# 09.net
KiCad netlist of a schematic drawn in Altium Designer
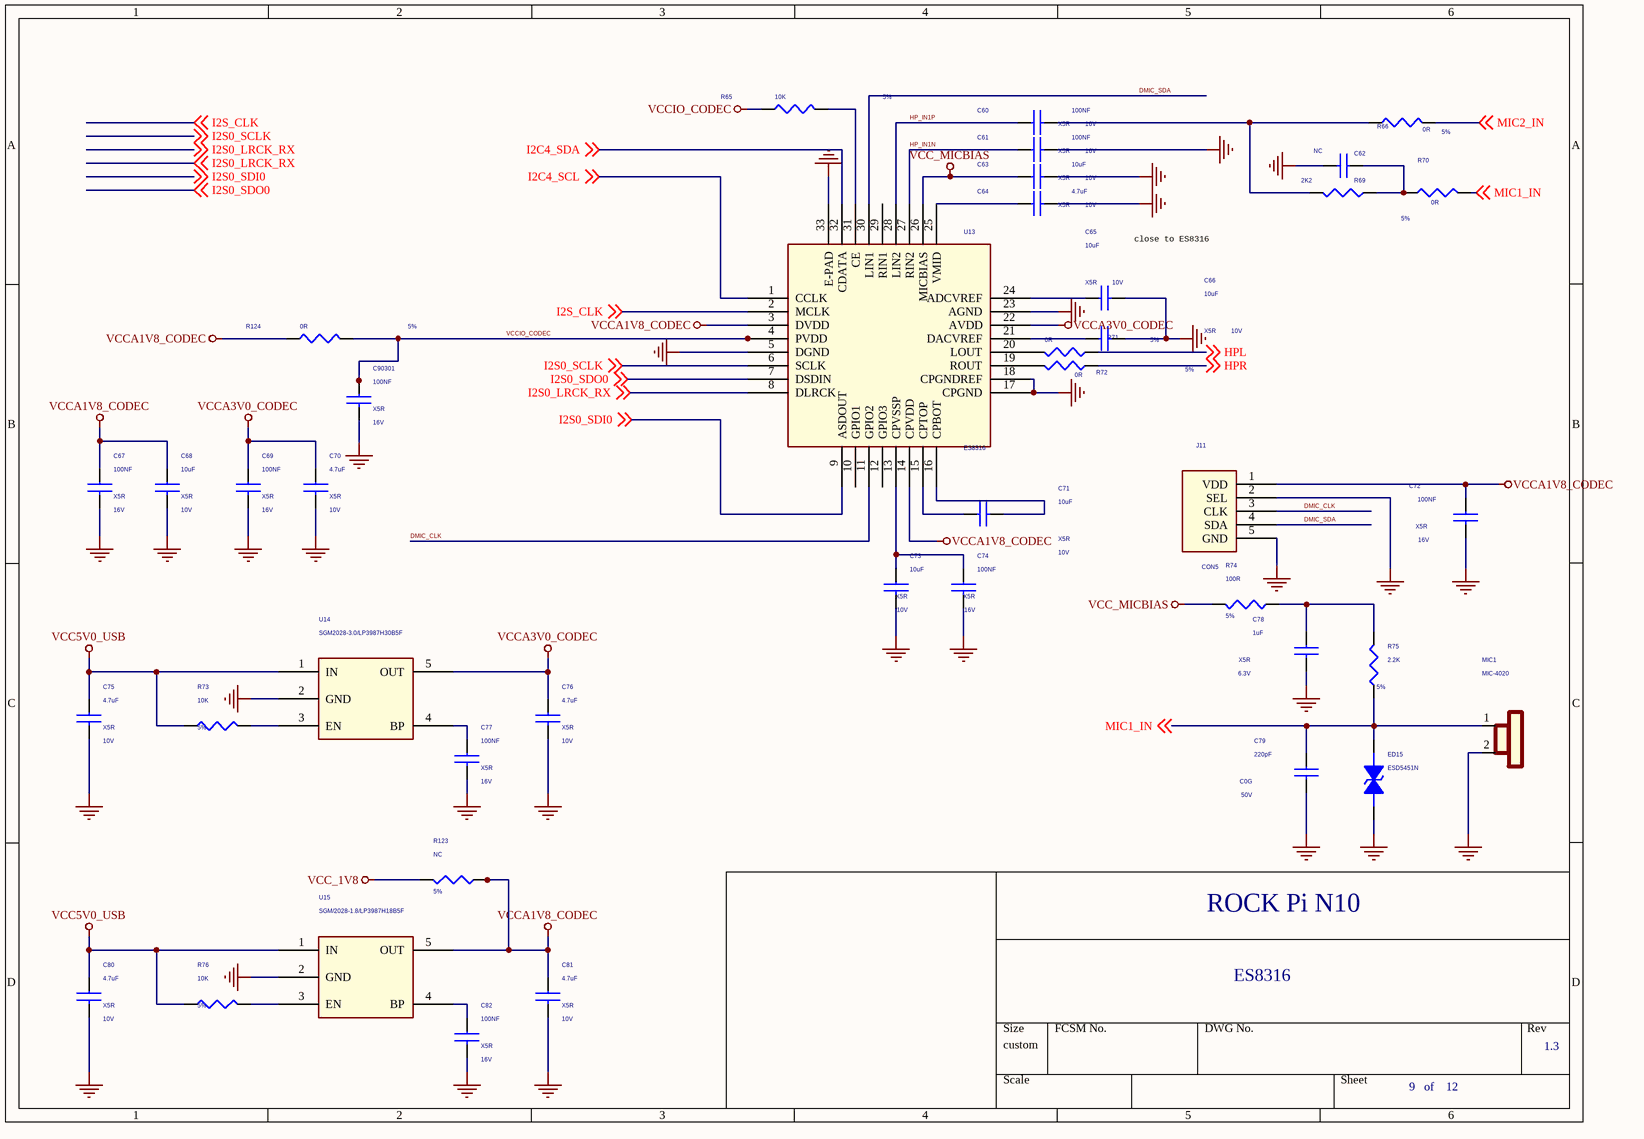
[diagram p0: 09.SchDoc]

(export (version "E")
  (design (tool "Eeschema 10.0.6"))
  (components
    (comp (ref "C60")
      (value "100NF")
      (footprint "C0402")
      (description "cap,100.00nF,+/-10%,16V,X5R,C0402")
      (fields
        (field (name "DIELECTRIC") "X5R")
        (field (name "VOLTAGE") "16V")
        (field (name "MANUFACTURER") "TDK")
        (field (name "TOLERANCE") "10%")
        (field (name "CREATED BY") "JJJ")
      )
      (libsource (lib "*") (part "CAP NP_2"))
    )
    (comp (ref "C61")
      (value "100NF")
      (footprint "C0402")
      (description "cap,100.00nF,+/-10%,16V,X5R,C0402")
      (fields
        (field (name "DIELECTRIC") "X5R")
        (field (name "VOLTAGE") "16V")
        (field (name "TOLERANCE") "10%")
        (field (name "MANUFACTURER") "TDK")
        (field (name "CREATED BY") "JJJ")
      )
      (libsource (lib "*") (part "CAP NP_2"))
    )
    (comp (ref "C62")
      (value "NC")
      (footprint "C0402")
      (description "RoHS CHIP CAP 0.1uF +10/-10% X7R")
      (libsource (lib "*") (part "CAP"))
    )
    (comp (ref "C63")
      (value "10uF")
      (footprint "C0603")
      (description "cap,10.00uF,+/-10%,10V,X5R,C0805")
      (fields
        (field (name "DIELECTRIC") "X5R")
        (field (name "VOLTAGE") "10V")
        (field (name "MANUFACTURER") "TDK")
        (field (name "TOLERANCE") "10%")
        (field (name "CREATED BY") "JJJ")
      )
      (libsource (lib "*") (part "CAP NP_2"))
    )
    (comp (ref "C64")
      (value "4.7uF")
      (footprint "C0402")
      (description "cap,4.70uF,+/-10%,10V,X5R,C0603")
      (fields
        (field (name "DIELECTRIC") "X5R")
        (field (name "VOLTAGE") "10V")
        (field (name "MANUFACTURER") "TDK")
        (field (name "TOLERANCE") "10%")
        (field (name "CREATED BY") "JJJ")
      )
      (libsource (lib "*") (part "CAP NP_2"))
    )
    (comp (ref "C65")
      (value "10uF")
      (footprint "C0603")
      (description "cap,10.00uF,+/-10%,10V,X5R,C0805")
      (fields
        (field (name "DIELECTRIC") "X5R")
        (field (name "VOLTAGE") "10V")
        (field (name "TOLERANCE") "10%")
        (field (name "MANUFACTURER") "TDK")
        (field (name "CREATED BY") "JJJ")
      )
      (libsource (lib "*") (part "CAP NP_2"))
    )
    (comp (ref "C66")
      (value "10uF")
      (footprint "C0603")
      (description "cap,10.00uF,+/-10%,10V,X5R,C0805")
      (fields
        (field (name "DIELECTRIC") "X5R")
        (field (name "VOLTAGE") "10V")
        (field (name "TOLERANCE") "10%")
        (field (name "MANUFACTURER") "TDK")
        (field (name "CREATED BY") "JJJ")
      )
      (libsource (lib "*") (part "CAP NP_2"))
    )
    (comp (ref "C67")
      (value "100NF")
      (footprint "C0402")
      (description "cap,100.00nF,+/-10%,16V,X5R,C0402")
      (fields
        (field (name "DIELECTRIC") "X5R")
        (field (name "VOLTAGE") "16V")
        (field (name "TOLERANCE") "10%")
        (field (name "MANUFACTURER") "TDK")
        (field (name "CREATED BY") "JJJ")
      )
      (libsource (lib "*") (part "CAP NP_2"))
    )
    (comp (ref "C68")
      (value "10uF")
      (footprint "C0603")
      (description "cap,10.00uF,+/-10%,10V,X5R,C0805")
      (fields
        (field (name "DIELECTRIC") "X5R")
        (field (name "VOLTAGE") "10V")
        (field (name "TOLERANCE") "10%")
        (field (name "MANUFACTURER") "TDK")
        (field (name "CREATED BY") "JJJ")
      )
      (libsource (lib "*") (part "CAP NP_2"))
    )
    (comp (ref "C69")
      (value "100NF")
      (footprint "C0402")
      (description "cap,100.00nF,+/-10%,16V,X5R,C0402")
      (fields
        (field (name "DIELECTRIC") "X5R")
        (field (name "VOLTAGE") "16V")
        (field (name "MANUFACTURER") "TDK")
        (field (name "TOLERANCE") "10%")
        (field (name "CREATED BY") "JJJ")
      )
      (libsource (lib "*") (part "CAP NP_2"))
    )
    (comp (ref "C70")
      (value "4.7uF")
      (footprint "C0402")
      (description "cap,4.70uF,+/-10%,10V,X5R,C0603")
      (fields
        (field (name "DIELECTRIC") "X5R")
        (field (name "VOLTAGE") "10V")
        (field (name "TOLERANCE") "10%")
        (field (name "MANUFACTURER") "TDK")
        (field (name "CREATED BY") "JJJ")
      )
      (libsource (lib "*") (part "CAP NP_2"))
    )
    (comp (ref "C71")
      (value "10uF")
      (footprint "C0603")
      (description "cap,10.00uF,+/-10%,10V,X5R,C0805")
      (fields
        (field (name "DIELECTRIC") "X5R")
        (field (name "VOLTAGE") "10V")
        (field (name "MANUFACTURER") "TDK")
        (field (name "TOLERANCE") "10%")
        (field (name "CREATED BY") "JJJ")
      )
      (libsource (lib "*") (part "CAP NP_2"))
    )
    (comp (ref "C72")
      (value "100NF")
      (footprint "C0402")
      (description "cap,100.00nF,+/-10%,16V,X5R,C0402")
      (fields
        (field (name "DIELECTRIC") "X5R")
        (field (name "VOLTAGE") "16V")
        (field (name "TOLERANCE") "10%")
        (field (name "MANUFACTURER") "TDK")
        (field (name "CREATED BY") "JJJ")
      )
      (libsource (lib "*") (part "CAP NP_2"))
    )
    (comp (ref "C73")
      (value "10uF")
      (footprint "C0603")
      (description "cap,10.00uF,+/-10%,10V,X5R,C0805")
      (fields
        (field (name "DIELECTRIC") "X5R")
        (field (name "VOLTAGE") "10V")
        (field (name "TOLERANCE") "10%")
        (field (name "MANUFACTURER") "TDK")
        (field (name "CREATED BY") "JJJ")
      )
      (libsource (lib "*") (part "CAP NP_2"))
    )
    (comp (ref "C74")
      (value "100NF")
      (footprint "C0402")
      (description "cap,100.00nF,+/-10%,16V,X5R,C0402")
      (fields
        (field (name "DIELECTRIC") "X5R")
        (field (name "VOLTAGE") "16V")
        (field (name "MANUFACTURER") "TDK")
        (field (name "TOLERANCE") "10%")
        (field (name "CREATED BY") "JJJ")
      )
      (libsource (lib "*") (part "CAP NP_2"))
    )
    (comp (ref "C75")
      (value "4.7uF")
      (footprint "C0603")
      (description "cap,4.70uF,+/-10%,10V,X5R,C0603")
      (fields
        (field (name "DIELECTRIC") "X5R")
        (field (name "VOLTAGE") "10V")
        (field (name "TOLERANCE") "10%")
        (field (name "MANUFACTURER") "TDK")
        (field (name "CREATED BY") "JJJ")
      )
      (libsource (lib "*") (part "CAP NP_2"))
    )
    (comp (ref "C76")
      (value "4.7uF")
      (footprint "C0603")
      (description "cap,4.70uF,+/-10%,10V,X5R,C0603")
      (fields
        (field (name "DIELECTRIC") "X5R")
        (field (name "VOLTAGE") "10V")
        (field (name "MANUFACTURER") "TDK")
        (field (name "TOLERANCE") "10%")
        (field (name "CREATED BY") "JJJ")
      )
      (libsource (lib "*") (part "CAP NP_2"))
    )
    (comp (ref "C77")
      (value "100NF")
      (footprint "C0402")
      (description "cap,100.00nF,+/-10%,16V,X5R,C0402")
      (fields
        (field (name "DIELECTRIC") "X5R")
        (field (name "VOLTAGE") "16V")
        (field (name "TOLERANCE") "10%")
        (field (name "MANUFACTURER") "TDK")
        (field (name "CREATED BY") "JJJ")
      )
      (libsource (lib "*") (part "CAP NP_2"))
    )
    (comp (ref "C78")
      (value "1uF")
      (footprint "C0402")
      (description "cap,1.00uF,+/-10%,6.3V,X5R,C0402")
      (fields
        (field (name "DIELECTRIC") "X5R")
        (field (name "VOLTAGE") "6.3V")
        (field (name "TOLERANCE") "10%")
        (field (name "MANUFACTURER") "TDK")
        (field (name "CREATED BY") "JJJ")
      )
      (libsource (lib "*") (part "CAP NP_2"))
    )
    (comp (ref "C79")
      (value "220pF")
      (footprint "C0402")
      (description "cap,220.00pF,+/-5%,50V,C0G,C0402")
      (fields
        (field (name "DIELECTRIC") "C0G")
        (field (name "VOLTAGE") "50V")
        (field (name "TOLERANCE") "5%")
        (field (name "MANUFACTURER") "TDK")
        (field (name "CREATED BY") "JJJ")
      )
      (libsource (lib "*") (part "CAP NP_2"))
    )
    (comp (ref "C80")
      (value "4.7uF")
      (footprint "C0603")
      (description "cap,4.70uF,+/-10%,10V,X5R,C0603")
      (fields
        (field (name "DIELECTRIC") "X5R")
        (field (name "VOLTAGE") "10V")
        (field (name "TOLERANCE") "10%")
        (field (name "MANUFACTURER") "TDK")
        (field (name "CREATED BY") "JJJ")
      )
      (libsource (lib "*") (part "CAP NP_2"))
    )
    (comp (ref "C81")
      (value "4.7uF")
      (footprint "C0603")
      (description "cap,4.70uF,+/-10%,10V,X5R,C0603")
      (fields
        (field (name "DIELECTRIC") "X5R")
        (field (name "VOLTAGE") "10V")
        (field (name "MANUFACTURER") "TDK")
        (field (name "TOLERANCE") "10%")
        (field (name "CREATED BY") "JJJ")
      )
      (libsource (lib "*") (part "CAP NP_2"))
    )
    (comp (ref "C82")
      (value "100NF")
      (footprint "C0402")
      (description "cap,100.00nF,+/-10%,16V,X5R,C0402")
      (fields
        (field (name "DIELECTRIC") "X5R")
        (field (name "VOLTAGE") "16V")
        (field (name "TOLERANCE") "10%")
        (field (name "MANUFACTURER") "TDK")
        (field (name "CREATED BY") "JJJ")
      )
      (libsource (lib "*") (part "CAP NP_2"))
    )
    (comp (ref "C90301")
      (value "100NF")
      (footprint "C0402")
      (description "cap,100.00nF,+/-10%,16V,X5R,C0402")
      (fields
        (field (name "DIELECTRIC") "X5R")
        (field (name "VOLTAGE") "16V")
        (field (name "MANUFACTURER") "TDK")
        (field (name "TOLERANCE") "10%")
        (field (name "CREATED BY") "JJJ")
      )
      (libsource (lib "*") (part "CAP NP_2"))
    )
    (comp (ref "ED15")
      (value "ESD5451N")
      (footprint "ESD0402")
      (description "1-Line, Bi-directional, Transient Voltage Suppressors.17.5pF.")
      (fields (field (name "MANUFACTURER") "WillSemi(韦尔半导体)") (field (name "CREATED BY") "JJJ"))
      (libsource (lib "*") (part "DIODE BI_DIR TRIG_0"))
    )
    (comp (ref "J11") (value "CON5") (footprint "SDO-4030") (libsource (lib "*") (part "CON5_0")))
    (comp (ref "MIC1")
      (value "MIC-4020")
      (footprint "CN1X2-1.25-SMT")
      (description "mic 咪头")
      (fields (field (name "MANUFACTURER") "待更新") (field (name "CREATED BY") "JJJ"))
      (libsource (lib "*") (part "MIC"))
    )
    (comp (ref "R65")
      (value "10K")
      (footprint "R0402")
      (description "通用厚膜电阻,10k,+/-5%,R0402,1/16W.")
      (fields
        (field (name "TOLERANCE") "5%")
        (field (name "MANUFACTURER") "YAGEO")
        (field (name "CREATED BY") "YTL")
      )
      (libsource (lib "*") (part "RESISTOR_3"))
    )
    (comp (ref "R66")
      (value "0R")
      (footprint "R0402")
      (description "通用厚膜电阻,22R,+/-5%,R0402,1/16W.")
      (fields
        (field (name "TOLERANCE") "5%")
        (field (name "MANUFACTURER") "YAGEO")
        (field (name "CREATED BY") "YTL")
      )
      (libsource (lib "*") (part "RESISTOR_3"))
    )
    (comp (ref "R69")
      (value "2K2")
      (footprint "R0402")
      (description "ROHS CHIP RES 2K2 1/16W 5%")
      (libsource (lib "*") (part "RESISTOR"))
    )
    (comp (ref "R70")
      (value "0R")
      (footprint "R0402")
      (description "通用厚膜电阻,22R,+/-5%,R0402,1/16W.")
      (fields
        (field (name "TOLERANCE") "5%")
        (field (name "MANUFACTURER") "YAGEO")
        (field (name "CREATED BY") "YTL")
      )
      (libsource (lib "*") (part "RESISTOR_3"))
    )
    (comp (ref "R71")
      (value "0R")
      (footprint "R0402")
      (description "通用厚膜电阻,22R,+/-5%,R0402,1/16W.")
      (fields
        (field (name "TOLERANCE") "5%")
        (field (name "MANUFACTURER") "YAGEO")
        (field (name "CREATED BY") "YTL")
      )
      (libsource (lib "*") (part "RESISTOR_3"))
    )
    (comp (ref "R72")
      (value "0R")
      (footprint "R0402")
      (description "通用厚膜电阻,22R,+/-5%,R0402,1/16W.")
      (fields
        (field (name "TOLERANCE") "5%")
        (field (name "MANUFACTURER") "YAGEO")
        (field (name "CREATED BY") "YTL")
      )
      (libsource (lib "*") (part "RESISTOR_3"))
    )
    (comp (ref "R73")
      (value "10K")
      (footprint "R0402")
      (description "通用厚膜电阻,10K,+/-5%,R0402,1/16W.")
      (fields
        (field (name "TOLERANCE") "5%")
        (field (name "MANUFACTURER") "YAGEO")
        (field (name "CREATED BY") "YTL")
      )
      (libsource (lib "*") (part "RESISTOR_3"))
    )
    (comp (ref "R74")
      (value "100R")
      (footprint "R0402")
      (description "通用厚膜电阻,100R,+/-5%,R0402,1/16W.")
      (fields
        (field (name "TOLERANCE") "5%")
        (field (name "MANUFACTURER") "YAGEO")
        (field (name "CREATED BY") "YTL")
      )
      (libsource (lib "*") (part "RESISTOR_3"))
    )
    (comp (ref "R75")
      (value "2.2K")
      (footprint "R0402")
      (description "通用厚膜电阻,2K2,+/-5%,R0402,1/16W.")
      (fields
        (field (name "TOLERANCE") "5%")
        (field (name "MANUFACTURER") "YAGEO")
        (field (name "CREATED BY") "YTL")
      )
      (libsource (lib "*") (part "RESISTOR_3"))
    )
    (comp (ref "R76")
      (value "10K")
      (footprint "R0402")
      (description "通用厚膜电阻,10K,+/-5%,R0402,1/16W.")
      (fields
        (field (name "TOLERANCE") "5%")
        (field (name "MANUFACTURER") "YAGEO")
        (field (name "CREATED BY") "YTL")
      )
      (libsource (lib "*") (part "RESISTOR_3"))
    )
    (comp (ref "R123")
      (value "NC")
      (footprint "R0402")
      (description "通用厚膜电阻,100R,+/-5%,R0402,1/16W.")
      (fields
        (field (name "TOLERANCE") "5%")
        (field (name "MANUFACTURER") "YAGEO")
        (field (name "CREATED BY") "YTL")
      )
      (libsource (lib "*") (part "RESISTOR_3"))
    )
    (comp (ref "R124")
      (value "0R")
      (footprint "R0402")
      (description "通用厚膜电阻,33R,+/-5%,R0402,1/16W.")
      (fields
        (field (name "TOLERANCE") "5%")
        (field (name "MANUFACTURER") "YAGEO")
        (field (name "CREATED BY") "YTL")
      )
      (libsource (lib "*") (part "RESISTOR_3"))
    )
    (comp (ref "U13")
      (value "ES8316")
      (footprint "QFN32P4X4")
      (description "Low Power Audio CODEC")
      (fields (field (name "MANUFACTURER") "Everest（顺芯）") (field (name "CREATED BY") "JJJ"))
      (libsource (lib "*") (part "CODEC_ES8316"))
    )
    (comp (ref "U14")
      (value "SGM2028-3.0/LP3987H30B5F")
      (footprint "SOT_23_5")
      (description "500mA, Low Dropout, Low Noise Ultra-Fast Without Bypass Capacitor CMOS LDO Regulator")
      (fields (field (name "MANUFACTURER") "Richtek（立錡）") (field (name "CREATED BY") "JJJ"))
      (libsource (lib "*") (part "LDO_PT5108"))
    )
    (comp (ref "U15")
      (value "SGM/2028-1.8/LP3987H18B5F")
      (footprint "SOT_23_5")
      (description "500mA, Low Dropout, Low Noise Ultra-Fast Without Bypass Capacitor CMOS LDO Regulator")
      (fields (field (name "MANUFACTURER") "Richtek（立錡）") (field (name "CREATED BY") "JJJ"))
      (libsource (lib "*") (part "LDO_PT5108"))
    )
  )
  (nets
    (net (code "1") (name "/DMIC_CLK") (class "Default")
      (node (ref "J11") (pin "3") (pinfunction "CLK_3") (pintype "passive"))
      (node (ref "U13") (pin "11") (pinfunction "GPIO2_11") (pintype "passive"))
    )
    (net (code "2") (name "/DMIC_SDA") (class "Default")
      (node (ref "J11") (pin "4") (pinfunction "SDA_4") (pintype "passive"))
      (node (ref "U13") (pin "30") (pinfunction "LIN1_30") (pintype "passive"))
    )
    (net (code "3") (name "/HP_IN1N") (class "Default")
      (node (ref "C61") (pin "1") (pinfunction "1_1") (pintype "passive"))
      (node (ref "U13") (pin "27") (pinfunction "RIN2_27") (pintype "passive"))
    )
    (net (code "4") (name "/HP_IN1P") (class "Default")
      (node (ref "C60") (pin "1") (pinfunction "1_1") (pintype "passive"))
      (node (ref "U13") (pin "28") (pinfunction "LIN2_28") (pintype "passive"))
    )
    (net (code "5") (name "GND") (class "Default")
      (node (ref "C61") (pin "2") (pinfunction "2_2") (pintype "passive"))
      (node (ref "C62") (pin "2") (pinfunction "2_2") (pintype "passive"))
      (node (ref "C63") (pin "2") (pinfunction "2_2") (pintype "passive"))
      (node (ref "C64") (pin "2") (pinfunction "2_2") (pintype "passive"))
      (node (ref "C65") (pin "2") (pinfunction "2_2") (pintype "passive"))
      (node (ref "C66") (pin "2") (pinfunction "2_2") (pintype "passive"))
      (node (ref "C67") (pin "2") (pinfunction "2_2") (pintype "passive"))
      (node (ref "C68") (pin "2") (pinfunction "2_2") (pintype "passive"))
      (node (ref "C69") (pin "2") (pinfunction "2_2") (pintype "passive"))
      (node (ref "C70") (pin "2") (pinfunction "2_2") (pintype "passive"))
      (node (ref "C72") (pin "2") (pinfunction "2_2") (pintype "passive"))
      (node (ref "C73") (pin "2") (pinfunction "2_2") (pintype "passive"))
      (node (ref "C74") (pin "2") (pinfunction "2_2") (pintype "passive"))
      (node (ref "C75") (pin "2") (pinfunction "2_2") (pintype "passive"))
      (node (ref "C76") (pin "2") (pinfunction "2_2") (pintype "passive"))
      (node (ref "C77") (pin "2") (pinfunction "2_2") (pintype "passive"))
      (node (ref "C78") (pin "2") (pinfunction "2_2") (pintype "passive"))
      (node (ref "C79") (pin "2") (pinfunction "2_2") (pintype "passive"))
      (node (ref "C80") (pin "2") (pinfunction "2_2") (pintype "passive"))
      (node (ref "C81") (pin "2") (pinfunction "2_2") (pintype "passive"))
      (node (ref "C82") (pin "2") (pinfunction "2_2") (pintype "passive"))
      (node (ref "C90301") (pin "2") (pinfunction "2_2") (pintype "passive"))
      (node (ref "ED15") (pin "2") (pinfunction "2_2") (pintype "passive"))
      (node (ref "J11") (pin "2") (pinfunction "SEL_2") (pintype "passive"))
      (node (ref "J11") (pin "5") (pinfunction "GND_5") (pintype "passive"))
      (node (ref "MIC1") (pin "2") (pinfunction "2_2") (pintype "passive"))
      (node (ref "U13") (pin "17") (pinfunction "CPGND_17") (pintype "passive"))
      (node (ref "U13") (pin "18") (pinfunction "CPGNDREF_18") (pintype "passive"))
      (node (ref "U13") (pin "23") (pinfunction "AGND_23") (pintype "passive"))
      (node (ref "U13") (pin "33") (pinfunction "E-PAD_33") (pintype "passive"))
      (node (ref "U13") (pin "5") (pinfunction "DGND_5") (pintype "passive"))
      (node (ref "U14") (pin "2") (pinfunction "GND_2") (pintype "passive"))
      (node (ref "U15") (pin "2") (pinfunction "GND_2") (pintype "passive"))
    )
    (net (code "6") (name "HPL") (class "Default")
      (node (ref "R71") (pin "1") (pinfunction "1_1") (pintype "passive"))
    )
    (net (code "7") (name "HPR") (class "Default")
      (node (ref "R72") (pin "1") (pinfunction "1_1") (pintype "passive"))
    )
    (net (code "8") (name "I2C4_SCL") (class "Default")
      (node (ref "U13") (pin "1") (pinfunction "CCLK_1") (pintype "passive"))
    )
    (net (code "9") (name "I2C4_SDA") (class "Default")
      (node (ref "U13") (pin "32") (pinfunction "CDATA_32") (pintype "passive"))
    )
    (net (code "10") (name "I2S0_LRCK_RX") (class "Default")
      (node (ref "U13") (pin "8") (pinfunction "DLRCK_8") (pintype "passive"))
    )
    (net (code "11") (name "I2S0_SCLK") (class "Default")
      (node (ref "U13") (pin "6") (pinfunction "SCLK_6") (pintype "passive"))
    )
    (net (code "12") (name "I2S0_SDI0") (class "Default")
      (node (ref "U13") (pin "9") (pinfunction "ASDOUT_9") (pintype "passive"))
    )
    (net (code "13") (name "I2S0_SDO0") (class "Default")
      (node (ref "U13") (pin "7") (pinfunction "DSDIN_7") (pintype "passive"))
    )
    (net (code "14") (name "I2S_CLK") (class "Default")
      (node (ref "U13") (pin "2") (pinfunction "MCLK_2") (pintype "passive"))
    )
    (net (code "15") (name "MIC1_IN") (class "Default")
      (node (ref "C79") (pin "1") (pinfunction "1_1") (pintype "passive"))
      (node (ref "ED15") (pin "1") (pinfunction "1_1") (pintype "passive"))
      (node (ref "MIC1") (pin "1") (pinfunction "1_1") (pintype "passive"))
      (node (ref "R70") (pin "2") (pinfunction "2_2") (pintype "passive"))
      (node (ref "R75") (pin "2") (pinfunction "2_2") (pintype "passive"))
    )
    (net (code "16") (name "MIC2_IN") (class "Default")
      (node (ref "R66") (pin "2") (pinfunction "2_2") (pintype "passive"))
    )
    (net (code "17") (name "Net-(C60-Pad2)") (class "Default")
      (node (ref "C60") (pin "2") (pinfunction "2_2") (pintype "passive"))
      (node (ref "R66") (pin "1") (pinfunction "1_1") (pintype "passive"))
      (node (ref "R69") (pin "1") (pinfunction "1_1") (pintype "passive"))
    )
    (net (code "18") (name "Net-(C62-Pad1)") (class "Default")
      (node (ref "C62") (pin "1") (pinfunction "1_1") (pintype "passive"))
      (node (ref "R69") (pin "2") (pinfunction "2_2") (pintype "passive"))
      (node (ref "R70") (pin "1") (pinfunction "1_1") (pintype "passive"))
    )
    (net (code "19") (name "Net-(C78-Pad1)") (class "Default")
      (node (ref "C78") (pin "1") (pinfunction "1_1") (pintype "passive"))
      (node (ref "R74") (pin "2") (pinfunction "2_2") (pintype "passive"))
      (node (ref "R75") (pin "1") (pinfunction "1_1") (pintype "passive"))
    )
    (net (code "20") (name "Net-(U13-ADCVREF)") (class "Default")
      (node (ref "C65") (pin "1") (pinfunction "1_1") (pintype "passive"))
      (node (ref "U13") (pin "24") (pinfunction "ADCVREF_24") (pintype "passive"))
    )
    (net (code "21") (name "Net-(U13-CE)") (class "Default")
      (node (ref "R65") (pin "2") (pinfunction "2_2") (pintype "passive"))
      (node (ref "U13") (pin "31") (pinfunction "CE_31") (pintype "passive"))
    )
    (net (code "22") (name "Net-(U13-CPBOT)") (class "Default")
      (node (ref "C71") (pin "2") (pinfunction "2_2") (pintype "passive"))
      (node (ref "U13") (pin "16") (pinfunction "CPBOT_16") (pintype "passive"))
    )
    (net (code "23") (name "Net-(U13-CPTOP)") (class "Default")
      (node (ref "C71") (pin "1") (pinfunction "1_1") (pintype "passive"))
      (node (ref "U13") (pin "15") (pinfunction "CPTOP_15") (pintype "passive"))
    )
    (net (code "24") (name "Net-(U13-CPVSSP)") (class "Default")
      (node (ref "C73") (pin "1") (pinfunction "1_1") (pintype "passive"))
      (node (ref "C74") (pin "1") (pinfunction "1_1") (pintype "passive"))
      (node (ref "U13") (pin "13") (pinfunction "CPVSSP_13") (pintype "passive"))
    )
    (net (code "25") (name "Net-(U13-DACVREF)") (class "Default")
      (node (ref "C66") (pin "1") (pinfunction "1_1") (pintype "passive"))
      (node (ref "U13") (pin "21") (pinfunction "DACVREF_21") (pintype "passive"))
    )
    (net (code "26") (name "Net-(U13-LOUT)") (class "Default")
      (node (ref "R71") (pin "2") (pinfunction "2_2") (pintype "passive"))
      (node (ref "U13") (pin "20") (pinfunction "LOUT_20") (pintype "passive"))
    )
    (net (code "27") (name "Net-(U13-ROUT)") (class "Default")
      (node (ref "R72") (pin "2") (pinfunction "2_2") (pintype "passive"))
      (node (ref "U13") (pin "19") (pinfunction "ROUT_19") (pintype "passive"))
    )
    (net (code "28") (name "Net-(U13-VMID)") (class "Default")
      (node (ref "C64") (pin "1") (pinfunction "1_1") (pintype "passive"))
      (node (ref "U13") (pin "25") (pinfunction "VMID_25") (pintype "passive"))
    )
    (net (code "29") (name "Net-(U14-BP)") (class "Default")
      (node (ref "C77") (pin "1") (pinfunction "1_1") (pintype "passive"))
      (node (ref "U14") (pin "4") (pinfunction "BP_4") (pintype "passive"))
    )
    (net (code "30") (name "Net-(U14-EN)") (class "Default")
      (node (ref "R73") (pin "2") (pinfunction "2_2") (pintype "passive"))
      (node (ref "U14") (pin "3") (pinfunction "EN_3") (pintype "passive"))
    )
    (net (code "31") (name "Net-(U15-BP)") (class "Default")
      (node (ref "C82") (pin "1") (pinfunction "1_1") (pintype "passive"))
      (node (ref "U15") (pin "4") (pinfunction "BP_4") (pintype "passive"))
    )
    (net (code "32") (name "Net-(U15-EN)") (class "Default")
      (node (ref "R76") (pin "2") (pinfunction "2_2") (pintype "passive"))
      (node (ref "U15") (pin "3") (pinfunction "EN_3") (pintype "passive"))
    )
    (net (code "33") (name "VCC5V0_USB") (class "Default")
      (node (ref "C75") (pin "1") (pinfunction "1_1") (pintype "passive"))
      (node (ref "C80") (pin "1") (pinfunction "1_1") (pintype "passive"))
      (node (ref "R73") (pin "1") (pinfunction "1_1") (pintype "passive"))
      (node (ref "R76") (pin "1") (pinfunction "1_1") (pintype "passive"))
      (node (ref "U14") (pin "1") (pinfunction "IN_1") (pintype "passive"))
      (node (ref "U15") (pin "1") (pinfunction "IN_1") (pintype "passive"))
    )
    (net (code "34") (name "VCCA1V8_CODEC") (class "Default")
      (node (ref "C67") (pin "1") (pinfunction "1_1") (pintype "passive"))
      (node (ref "C68") (pin "1") (pinfunction "1_1") (pintype "passive"))
      (node (ref "C72") (pin "1") (pinfunction "1_1") (pintype "passive"))
      (node (ref "C81") (pin "1") (pinfunction "1_1") (pintype "passive"))
      (node (ref "J11") (pin "1") (pinfunction "VDD_1") (pintype "passive"))
      (node (ref "R123") (pin "2") (pinfunction "2_2") (pintype "passive"))
      (node (ref "R124") (pin "1") (pinfunction "1_1") (pintype "passive"))
      (node (ref "U13") (pin "14") (pinfunction "CPVDD_14") (pintype "passive"))
      (node (ref "U13") (pin "3") (pinfunction "DVDD_3") (pintype "passive"))
      (node (ref "U15") (pin "5") (pinfunction "OUT_5") (pintype "passive"))
    )
    (net (code "35") (name "VCCA3V0_CODEC") (class "Default")
      (node (ref "C69") (pin "1") (pinfunction "1_1") (pintype "passive"))
      (node (ref "C70") (pin "1") (pinfunction "1_1") (pintype "passive"))
      (node (ref "C76") (pin "1") (pinfunction "1_1") (pintype "passive"))
      (node (ref "U13") (pin "22") (pinfunction "AVDD_22") (pintype "passive"))
      (node (ref "U14") (pin "5") (pinfunction "OUT_5") (pintype "passive"))
    )
    (net (code "36") (name "VCCIO_CODEC") (class "Default")
      (node (ref "C90301") (pin "1") (pinfunction "1_1") (pintype "passive"))
      (node (ref "R124") (pin "2") (pinfunction "2_2") (pintype "passive"))
      (node (ref "R65") (pin "1") (pinfunction "1_1") (pintype "passive"))
      (node (ref "U13") (pin "4") (pinfunction "PVDD_4") (pintype "passive"))
    )
    (net (code "37") (name "VCC_1V8") (class "Default")
      (node (ref "R123") (pin "1") (pinfunction "1_1") (pintype "passive"))
    )
    (net (code "38") (name "VCC_MICBIAS") (class "Default")
      (node (ref "C63") (pin "1") (pinfunction "1_1") (pintype "passive"))
      (node (ref "R74") (pin "1") (pinfunction "1_1") (pintype "passive"))
      (node (ref "U13") (pin "26") (pinfunction "MICBIAS_26") (pintype "passive"))
    )
    (net (code "39") (name "unconnected-(U13-GPIO1-Pad10)") (class "Default")
      (node (ref "U13") (pin "10") (pinfunction "GPIO1_10") (pintype "passive"))
    )
    (net (code "40") (name "unconnected-(U13-GPIO3-Pad12)") (class "Default")
      (node (ref "U13") (pin "12") (pinfunction "GPIO3_12") (pintype "passive"))
    )
    (net (code "41") (name "unconnected-(U13-RIN1-Pad29)") (class "Default")
      (node (ref "U13") (pin "29") (pinfunction "RIN1_29") (pintype "passive"))
    )
  )
)
